# sketch_identifier.net
KiCad netlist of a schematic drawn in Altium Designer
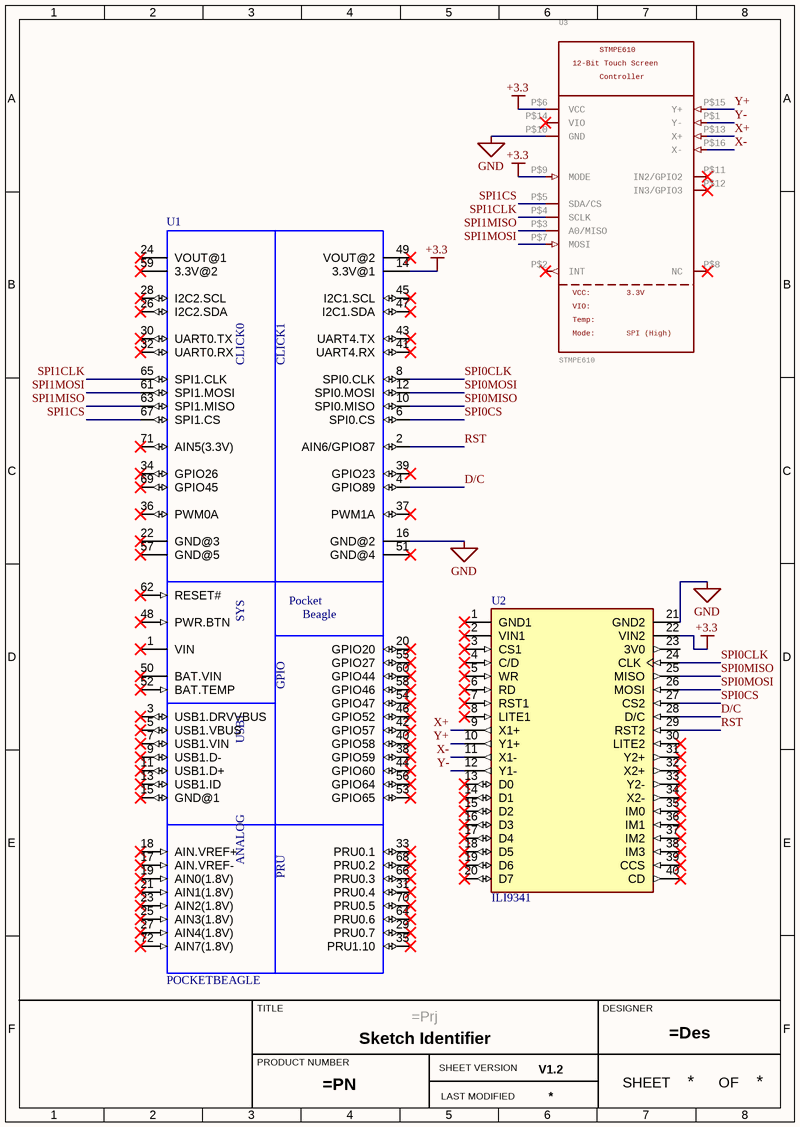
[diagram p0: sketch identifier.SchDoc]

(export (version "E")
  (design (tool "Eeschema 10.0.6"))
  (components
    (comp (ref "U1")
      (value "POCKETBEAGLE")
      (footprint "POCKETBEAGLE")
      (description "OSD3358 PocketBeagle - ARMÂ® CortexÂ®-A8 MPU Embedded Evaluation Board")
      (fields (field (name "MF") "Beagleboard"))
      (libsource (lib "Winson Lin") (part "POCKETBEAGLE"))
    )
    (comp (ref "U2")
      (value "ILI9341")
      (footprint "ADAFRUIT_2478")
      (fields (field (name "MP") "2478") (field (name "MF") "Adafruit Industries"))
      (libsource (lib "Winson Lin") (part "2478"))
    )
    (comp (ref "U3")
      (value "STMPE610")
      (footprint "QFN16_3MM")
      (description "STMPE610 - 12-Bit Touch Screen Controller")
      (fields
        (field (name "VCC") "VCC:")
        (field (name "1.8-3.6V") "3.3V")
        (field (name "VIO") "VIO:")
        (field (name "TEMP") "Temp:")
        (field (name "STMPE610") "STMPE610")
        (field (name "12-BITTOUCHSCREEN") "12-Bit Touch Screen")
        (field (name "CONTROLLER") "Controller")
        (field (name "MODE") "Mode:")
      )
      (libsource (lib "Winson Lin") (part "STMPE610"))
    )
  )
  (nets
    (net (code "1") (name "+3.3") (class "Default")
      (node (ref "U1") (pin "14") (pinfunction "3.3V@1_14") (pintype "power_in"))
      (node (ref "U2") (pin "22") (pinfunction "VIN2_22") (pintype "power_in"))
      (node (ref "U3") (pin "P$6") (pinfunction "VCC_P$6") (pintype "power_in"))
      (node (ref "U3") (pin "P$9") (pinfunction "MODE_P$9") (pintype "input"))
    )
    (net (code "2") (name "/D{slash}C") (class "Default")
      (node (ref "U1") (pin "4") (pinfunction "GPIO89_4") (pintype "bidirectional"))
      (node (ref "U2") (pin "28") (pinfunction "D/C_28") (pintype "input"))
    )
    (net (code "3") (name "/RST") (class "Default")
      (node (ref "U1") (pin "2") (pinfunction "AIN6/GPIO87_2") (pintype "bidirectional"))
      (node (ref "U2") (pin "29") (pinfunction "RST2_29") (pintype "input"))
    )
    (net (code "4") (name "/SPI0CLK") (class "Default")
      (node (ref "U1") (pin "8") (pinfunction "SPI0.CLK_8") (pintype "bidirectional"))
      (node (ref "U2") (pin "24") (pinfunction "CLK_24") (pintype "input"))
    )
    (net (code "5") (name "/SPI0CS") (class "Default")
      (node (ref "U1") (pin "6") (pinfunction "SPI0.CS_6") (pintype "bidirectional"))
      (node (ref "U2") (pin "27") (pinfunction "CS2_27") (pintype "input"))
    )
    (net (code "6") (name "/SPI0MISO") (class "Default")
      (node (ref "U1") (pin "10") (pinfunction "SPI0.MISO_10") (pintype "bidirectional"))
      (node (ref "U2") (pin "25") (pinfunction "MISO_25") (pintype "output"))
    )
    (net (code "7") (name "/SPI0MOSI") (class "Default")
      (node (ref "U1") (pin "12") (pinfunction "SPI0.MOSI_12") (pintype "bidirectional"))
      (node (ref "U2") (pin "26") (pinfunction "MOSI_26") (pintype "input"))
    )
    (net (code "8") (name "/SPI1CLK") (class "Default")
      (node (ref "U1") (pin "65") (pinfunction "SPI1.CLK_65") (pintype "bidirectional"))
      (node (ref "U3") (pin "P$4") (pinfunction "SCLK_P$4") (pintype "bidirectional"))
    )
    (net (code "9") (name "/SPI1CS") (class "Default")
      (node (ref "U1") (pin "67") (pinfunction "SPI1.CS_67") (pintype "bidirectional"))
      (node (ref "U3") (pin "P$5") (pinfunction "SDA/CS_P$5") (pintype "bidirectional"))
    )
    (net (code "10") (name "/SPI1MISO") (class "Default")
      (node (ref "U1") (pin "63") (pinfunction "SPI1.MISO_63") (pintype "bidirectional"))
      (node (ref "U3") (pin "P$3") (pinfunction "A0/MISO_P$3") (pintype "bidirectional"))
    )
    (net (code "11") (name "/SPI1MOSI") (class "Default")
      (node (ref "U1") (pin "61") (pinfunction "SPI1.MOSI_61") (pintype "bidirectional"))
      (node (ref "U3") (pin "P$7") (pinfunction "MOSI_P$7") (pintype "input"))
    )
    (net (code "12") (name "/X+") (class "Default")
      (node (ref "U2") (pin "9") (pinfunction "X1+_9") (pintype "output"))
      (node (ref "U3") (pin "P$13") (pinfunction "X+_P$13") (pintype "input"))
    )
    (net (code "13") (name "/X-") (class "Default")
      (node (ref "U2") (pin "11") (pinfunction "X1-_11") (pintype "output"))
      (node (ref "U3") (pin "P$16") (pinfunction "X-_P$16") (pintype "input"))
    )
    (net (code "14") (name "/Y+") (class "Default")
      (node (ref "U2") (pin "10") (pinfunction "Y1+_10") (pintype "output"))
      (node (ref "U3") (pin "P$15") (pinfunction "Y+_P$15") (pintype "input"))
    )
    (net (code "15") (name "/Y-") (class "Default")
      (node (ref "U2") (pin "12") (pinfunction "Y1-_12") (pintype "output"))
      (node (ref "U3") (pin "P$1") (pinfunction "Y-_P$1") (pintype "input"))
    )
    (net (code "16") (name "GND") (class "Default")
      (node (ref "U1") (pin "16") (pinfunction "GND@2_16") (pintype "power_in"))
      (node (ref "U2") (pin "21") (pinfunction "GND2_21") (pintype "power_in"))
      (node (ref "U3") (pin "P$10") (pinfunction "GND_P$10") (pintype "power_in"))
    )
    (net (code "17") (name "unconnected-(U1-3.3V@2-Pad59)") (class "Default")
      (node (ref "U1") (pin "59") (pinfunction "3.3V@2_59") (pintype "power_in+no_connect"))
    )
    (net (code "18") (name "unconnected-(U1-AIN.VREF+-Pad18)") (class "Default")
      (node (ref "U1") (pin "18") (pinfunction "AIN.VREF+_18") (pintype "input+no_connect"))
    )
    (net (code "19") (name "unconnected-(U1-AIN.VREF--Pad17)") (class "Default")
      (node (ref "U1") (pin "17") (pinfunction "AIN.VREF-_17") (pintype "input+no_connect"))
    )
    (net (code "20") (name "unconnected-(U1-AIN0(1.8V)-Pad19)") (class "Default")
      (node (ref "U1") (pin "19") (pinfunction "AIN0(1.8V)_19") (pintype "input+no_connect"))
    )
    (net (code "21") (name "unconnected-(U1-AIN1(1.8V)-Pad21)") (class "Default")
      (node (ref "U1") (pin "21") (pinfunction "AIN1(1.8V)_21") (pintype "input+no_connect"))
    )
    (net (code "22") (name "unconnected-(U1-AIN2(1.8V)-Pad23)") (class "Default")
      (node (ref "U1") (pin "23") (pinfunction "AIN2(1.8V)_23") (pintype "input+no_connect"))
    )
    (net (code "23") (name "unconnected-(U1-AIN3(1.8V)-Pad25)") (class "Default")
      (node (ref "U1") (pin "25") (pinfunction "AIN3(1.8V)_25") (pintype "input+no_connect"))
    )
    (net (code "24") (name "unconnected-(U1-AIN4(1.8V)-Pad27)") (class "Default")
      (node (ref "U1") (pin "27") (pinfunction "AIN4(1.8V)_27") (pintype "input+no_connect"))
    )
    (net (code "25") (name "unconnected-(U1-AIN5(3.3V)-Pad71)") (class "Default")
      (node (ref "U1") (pin "71") (pinfunction "AIN5(3.3V)_71") (pintype "bidirectional+no_connect"))
    )
    (net (code "26") (name "unconnected-(U1-AIN7(1.8V)-Pad72)") (class "Default")
      (node (ref "U1") (pin "72") (pinfunction "AIN7(1.8V)_72") (pintype "input+no_connect"))
    )
    (net (code "27") (name "unconnected-(U1-BAT.TEMP-Pad52)") (class "Default")
      (node (ref "U1") (pin "52") (pinfunction "BAT.TEMP_52") (pintype "input+no_connect"))
    )
    (net (code "28") (name "unconnected-(U1-BAT.VIN-Pad50)") (class "Default")
      (node (ref "U1") (pin "50") (pinfunction "BAT.VIN_50") (pintype "power_in+no_connect"))
    )
    (net (code "29") (name "unconnected-(U1-GND@1-Pad15)") (class "Default")
      (node (ref "U1") (pin "15") (pinfunction "GND@1_15") (pintype "bidirectional+no_connect"))
    )
    (net (code "30") (name "unconnected-(U1-GND@3-Pad22)") (class "Default")
      (node (ref "U1") (pin "22") (pinfunction "GND@3_22") (pintype "power_in+no_connect"))
    )
    (net (code "31") (name "unconnected-(U1-GND@4-Pad51)") (class "Default")
      (node (ref "U1") (pin "51") (pinfunction "GND@4_51") (pintype "power_in+no_connect"))
    )
    (net (code "32") (name "unconnected-(U1-GND@5-Pad57)") (class "Default")
      (node (ref "U1") (pin "57") (pinfunction "GND@5_57") (pintype "power_in+no_connect"))
    )
    (net (code "33") (name "unconnected-(U1-GPIO20-Pad20)") (class "Default")
      (node (ref "U1") (pin "20") (pinfunction "GPIO20_20") (pintype "bidirectional+no_connect"))
    )
    (net (code "34") (name "unconnected-(U1-GPIO23-Pad39)") (class "Default")
      (node (ref "U1") (pin "39") (pinfunction "GPIO23_39") (pintype "bidirectional+no_connect"))
    )
    (net (code "35") (name "unconnected-(U1-GPIO26-Pad34)") (class "Default")
      (node (ref "U1") (pin "34") (pinfunction "GPIO26_34") (pintype "bidirectional+no_connect"))
    )
    (net (code "36") (name "unconnected-(U1-GPIO27-Pad55)") (class "Default")
      (node (ref "U1") (pin "55") (pinfunction "GPIO27_55") (pintype "bidirectional+no_connect"))
    )
    (net (code "37") (name "unconnected-(U1-GPIO44-Pad60)") (class "Default")
      (node (ref "U1") (pin "60") (pinfunction "GPIO44_60") (pintype "bidirectional+no_connect"))
    )
    (net (code "38") (name "unconnected-(U1-GPIO45-Pad69)") (class "Default")
      (node (ref "U1") (pin "69") (pinfunction "GPIO45_69") (pintype "bidirectional+no_connect"))
    )
    (net (code "39") (name "unconnected-(U1-GPIO46-Pad58)") (class "Default")
      (node (ref "U1") (pin "58") (pinfunction "GPIO46_58") (pintype "bidirectional+no_connect"))
    )
    (net (code "40") (name "unconnected-(U1-GPIO47-Pad54)") (class "Default")
      (node (ref "U1") (pin "54") (pinfunction "GPIO47_54") (pintype "bidirectional+no_connect"))
    )
    (net (code "41") (name "unconnected-(U1-GPIO52-Pad46)") (class "Default")
      (node (ref "U1") (pin "46") (pinfunction "GPIO52_46") (pintype "bidirectional+no_connect"))
    )
    (net (code "42") (name "unconnected-(U1-GPIO57-Pad42)") (class "Default")
      (node (ref "U1") (pin "42") (pinfunction "GPIO57_42") (pintype "bidirectional+no_connect"))
    )
    (net (code "43") (name "unconnected-(U1-GPIO58-Pad40)") (class "Default")
      (node (ref "U1") (pin "40") (pinfunction "GPIO58_40") (pintype "bidirectional+no_connect"))
    )
    (net (code "44") (name "unconnected-(U1-GPIO59-Pad38)") (class "Default")
      (node (ref "U1") (pin "38") (pinfunction "GPIO59_38") (pintype "bidirectional+no_connect"))
    )
    (net (code "45") (name "unconnected-(U1-GPIO60-Pad44)") (class "Default")
      (node (ref "U1") (pin "44") (pinfunction "GPIO60_44") (pintype "bidirectional+no_connect"))
    )
    (net (code "46") (name "unconnected-(U1-GPIO64-Pad56)") (class "Default")
      (node (ref "U1") (pin "56") (pinfunction "GPIO64_56") (pintype "bidirectional+no_connect"))
    )
    (net (code "47") (name "unconnected-(U1-GPIO65-Pad53)") (class "Default")
      (node (ref "U1") (pin "53") (pinfunction "GPIO65_53") (pintype "bidirectional+no_connect"))
    )
    (net (code "48") (name "unconnected-(U1-I2C1.SCL-Pad45)") (class "Default")
      (node (ref "U1") (pin "45") (pinfunction "I2C1.SCL_45") (pintype "bidirectional+no_connect"))
    )
    (net (code "49") (name "unconnected-(U1-I2C1.SDA-Pad47)") (class "Default")
      (node (ref "U1") (pin "47") (pinfunction "I2C1.SDA_47") (pintype "bidirectional+no_connect"))
    )
    (net (code "50") (name "unconnected-(U1-I2C2.SCL-Pad28)") (class "Default")
      (node (ref "U1") (pin "28") (pinfunction "I2C2.SCL_28") (pintype "bidirectional+no_connect"))
    )
    (net (code "51") (name "unconnected-(U1-I2C2.SDA-Pad26)") (class "Default")
      (node (ref "U1") (pin "26") (pinfunction "I2C2.SDA_26") (pintype "bidirectional+no_connect"))
    )
    (net (code "52") (name "unconnected-(U1-PRU0.1-Pad33)") (class "Default")
      (node (ref "U1") (pin "33") (pinfunction "PRU0.1_33") (pintype "bidirectional+no_connect"))
    )
    (net (code "53") (name "unconnected-(U1-PRU0.2-Pad68)") (class "Default")
      (node (ref "U1") (pin "68") (pinfunction "PRU0.2_68") (pintype "bidirectional+no_connect"))
    )
    (net (code "54") (name "unconnected-(U1-PRU0.3-Pad66)") (class "Default")
      (node (ref "U1") (pin "66") (pinfunction "PRU0.3_66") (pintype "bidirectional+no_connect"))
    )
    (net (code "55") (name "unconnected-(U1-PRU0.4-Pad31)") (class "Default")
      (node (ref "U1") (pin "31") (pinfunction "PRU0.4_31") (pintype "bidirectional+no_connect"))
    )
    (net (code "56") (name "unconnected-(U1-PRU0.5-Pad70)") (class "Default")
      (node (ref "U1") (pin "70") (pinfunction "PRU0.5_70") (pintype "bidirectional+no_connect"))
    )
    (net (code "57") (name "unconnected-(U1-PRU0.6-Pad64)") (class "Default")
      (node (ref "U1") (pin "64") (pinfunction "PRU0.6_64") (pintype "bidirectional+no_connect"))
    )
    (net (code "58") (name "unconnected-(U1-PRU0.7-Pad29)") (class "Default")
      (node (ref "U1") (pin "29") (pinfunction "PRU0.7_29") (pintype "bidirectional+no_connect"))
    )
    (net (code "59") (name "unconnected-(U1-PRU1.10-Pad35)") (class "Default")
      (node (ref "U1") (pin "35") (pinfunction "PRU1.10_35") (pintype "bidirectional+no_connect"))
    )
    (net (code "60") (name "unconnected-(U1-PWM0A-Pad36)") (class "Default")
      (node (ref "U1") (pin "36") (pinfunction "PWM0A_36") (pintype "bidirectional+no_connect"))
    )
    (net (code "61") (name "unconnected-(U1-PWM1A-Pad37)") (class "Default")
      (node (ref "U1") (pin "37") (pinfunction "PWM1A_37") (pintype "bidirectional+no_connect"))
    )
    (net (code "62") (name "unconnected-(U1-PWR.BTN-Pad48)") (class "Default")
      (node (ref "U1") (pin "48") (pinfunction "PWR.BTN_48") (pintype "input+no_connect"))
    )
    (net (code "63") (name "unconnected-(U1-RESET#-Pad62)") (class "Default")
      (node (ref "U1") (pin "62") (pinfunction "RESET#_62") (pintype "input+no_connect"))
    )
    (net (code "64") (name "unconnected-(U1-UART0.RX-Pad32)") (class "Default")
      (node (ref "U1") (pin "32") (pinfunction "UART0.RX_32") (pintype "bidirectional+no_connect"))
    )
    (net (code "65") (name "unconnected-(U1-UART0.TX-Pad30)") (class "Default")
      (node (ref "U1") (pin "30") (pinfunction "UART0.TX_30") (pintype "bidirectional+no_connect"))
    )
    (net (code "66") (name "unconnected-(U1-UART4.RX-Pad41)") (class "Default")
      (node (ref "U1") (pin "41") (pinfunction "UART4.RX_41") (pintype "bidirectional+no_connect"))
    )
    (net (code "67") (name "unconnected-(U1-UART4.TX-Pad43)") (class "Default")
      (node (ref "U1") (pin "43") (pinfunction "UART4.TX_43") (pintype "bidirectional+no_connect"))
    )
    (net (code "68") (name "unconnected-(U1-USB1.D+-Pad11)") (class "Default")
      (node (ref "U1") (pin "11") (pinfunction "USB1.D+_11") (pintype "bidirectional+no_connect"))
    )
    (net (code "69") (name "unconnected-(U1-USB1.D--Pad9)") (class "Default")
      (node (ref "U1") (pin "9") (pinfunction "USB1.D-_9") (pintype "bidirectional+no_connect"))
    )
    (net (code "70") (name "unconnected-(U1-USB1.DRVVBUS-Pad3)") (class "Default")
      (node (ref "U1") (pin "3") (pinfunction "USB1.DRVVBUS_3") (pintype "bidirectional+no_connect"))
    )
    (net (code "71") (name "unconnected-(U1-USB1.ID-Pad13)") (class "Default")
      (node (ref "U1") (pin "13") (pinfunction "USB1.ID_13") (pintype "bidirectional+no_connect"))
    )
    (net (code "72") (name "unconnected-(U1-USB1.VBUS-Pad5)") (class "Default")
      (node (ref "U1") (pin "5") (pinfunction "USB1.VBUS_5") (pintype "bidirectional+no_connect"))
    )
    (net (code "73") (name "unconnected-(U1-USB1.VIN-Pad7)") (class "Default")
      (node (ref "U1") (pin "7") (pinfunction "USB1.VIN_7") (pintype "bidirectional+no_connect"))
    )
    (net (code "74") (name "unconnected-(U1-VIN-Pad1)") (class "Default")
      (node (ref "U1") (pin "1") (pinfunction "VIN_1") (pintype "power_in+no_connect"))
    )
    (net (code "75") (name "unconnected-(U1-VOUT@1-Pad24)") (class "Default")
      (node (ref "U1") (pin "24") (pinfunction "VOUT@1_24") (pintype "power_in+no_connect"))
    )
    (net (code "76") (name "unconnected-(U1-VOUT@2-Pad49)") (class "Default")
      (node (ref "U1") (pin "49") (pinfunction "VOUT@2_49") (pintype "power_in+no_connect"))
    )
    (net (code "77") (name "unconnected-(U2-3V0-Pad23)") (class "Default")
      (node (ref "U2") (pin "23") (pinfunction "3V0_23") (pintype "output"))
    )
    (net (code "78") (name "unconnected-(U2-CCS-Pad39)") (class "Default")
      (node (ref "U2") (pin "39") (pinfunction "CCS_39") (pintype "input+no_connect"))
    )
    (net (code "79") (name "unconnected-(U2-CD-Pad40)") (class "Default")
      (node (ref "U2") (pin "40") (pinfunction "CD_40") (pintype "output+no_connect"))
    )
    (net (code "80") (name "unconnected-(U2-CS1-Pad3)") (class "Default")
      (node (ref "U2") (pin "3") (pinfunction "CS1_3") (pintype "input+no_connect"))
    )
    (net (code "81") (name "unconnected-(U2-C{slash}D-Pad4)") (class "Default")
      (node (ref "U2") (pin "4") (pinfunction "C/D_4") (pintype "input+no_connect"))
    )
    (net (code "82") (name "unconnected-(U2-D0-Pad13)") (class "Default")
      (node (ref "U2") (pin "13") (pinfunction "D0_13") (pintype "bidirectional+no_connect"))
    )
    (net (code "83") (name "unconnected-(U2-D1-Pad14)") (class "Default")
      (node (ref "U2") (pin "14") (pinfunction "D1_14") (pintype "bidirectional+no_connect"))
    )
    (net (code "84") (name "unconnected-(U2-D2-Pad15)") (class "Default")
      (node (ref "U2") (pin "15") (pinfunction "D2_15") (pintype "bidirectional+no_connect"))
    )
    (net (code "85") (name "unconnected-(U2-D3-Pad16)") (class "Default")
      (node (ref "U2") (pin "16") (pinfunction "D3_16") (pintype "bidirectional+no_connect"))
    )
    (net (code "86") (name "unconnected-(U2-D4-Pad17)") (class "Default")
      (node (ref "U2") (pin "17") (pinfunction "D4_17") (pintype "bidirectional+no_connect"))
    )
    (net (code "87") (name "unconnected-(U2-D5-Pad18)") (class "Default")
      (node (ref "U2") (pin "18") (pinfunction "D5_18") (pintype "bidirectional+no_connect"))
    )
    (net (code "88") (name "unconnected-(U2-D6-Pad19)") (class "Default")
      (node (ref "U2") (pin "19") (pinfunction "D6_19") (pintype "bidirectional+no_connect"))
    )
    (net (code "89") (name "unconnected-(U2-D7-Pad20)") (class "Default")
      (node (ref "U2") (pin "20") (pinfunction "D7_20") (pintype "bidirectional+no_connect"))
    )
    (net (code "90") (name "unconnected-(U2-GND1-Pad1)") (class "Default")
      (node (ref "U2") (pin "1") (pinfunction "GND1_1") (pintype "power_in+no_connect"))
    )
    (net (code "91") (name "unconnected-(U2-IM0-Pad35)") (class "Default")
      (node (ref "U2") (pin "35") (pinfunction "IM0_35") (pintype "input+no_connect"))
    )
    (net (code "92") (name "unconnected-(U2-IM1-Pad36)") (class "Default")
      (node (ref "U2") (pin "36") (pinfunction "IM1_36") (pintype "input+no_connect"))
    )
    (net (code "93") (name "unconnected-(U2-IM2-Pad37)") (class "Default")
      (node (ref "U2") (pin "37") (pinfunction "IM2_37") (pintype "input+no_connect"))
    )
    (net (code "94") (name "unconnected-(U2-IM3-Pad38)") (class "Default")
      (node (ref "U2") (pin "38") (pinfunction "IM3_38") (pintype "input+no_connect"))
    )
    (net (code "95") (name "unconnected-(U2-LITE1-Pad8)") (class "Default")
      (node (ref "U2") (pin "8") (pinfunction "LITE1_8") (pintype "input+no_connect"))
    )
    (net (code "96") (name "unconnected-(U2-LITE2-Pad30)") (class "Default")
      (node (ref "U2") (pin "30") (pinfunction "LITE2_30") (pintype "input+no_connect"))
    )
    (net (code "97") (name "unconnected-(U2-RD-Pad6)") (class "Default")
      (node (ref "U2") (pin "6") (pinfunction "RD_6") (pintype "input+no_connect"))
    )
    (net (code "98") (name "unconnected-(U2-RST1-Pad7)") (class "Default")
      (node (ref "U2") (pin "7") (pinfunction "RST1_7") (pintype "input+no_connect"))
    )
    (net (code "99") (name "unconnected-(U2-VIN1-Pad2)") (class "Default")
      (node (ref "U2") (pin "2") (pinfunction "VIN1_2") (pintype "power_in+no_connect"))
    )
    (net (code "100") (name "unconnected-(U2-WR-Pad5)") (class "Default")
      (node (ref "U2") (pin "5") (pinfunction "WR_5") (pintype "input+no_connect"))
    )
    (net (code "101") (name "unconnected-(U2-X2+-Pad32)") (class "Default")
      (node (ref "U2") (pin "32") (pinfunction "X2+_32") (pintype "output+no_connect"))
    )
    (net (code "102") (name "unconnected-(U2-X2--Pad34)") (class "Default")
      (node (ref "U2") (pin "34") (pinfunction "X2-_34") (pintype "output+no_connect"))
    )
    (net (code "103") (name "unconnected-(U2-Y2+-Pad31)") (class "Default")
      (node (ref "U2") (pin "31") (pinfunction "Y2+_31") (pintype "output+no_connect"))
    )
    (net (code "104") (name "unconnected-(U2-Y2--Pad33)") (class "Default")
      (node (ref "U2") (pin "33") (pinfunction "Y2-_33") (pintype "output+no_connect"))
    )
    (net (code "105") (name "unconnected-(U3-IN2{slash}GPIO2-PadP$11)") (class "Default")
      (node (ref "U3") (pin "P$11") (pinfunction "IN2/GPIO2_P$11") (pintype "bidirectional+no_connect"))
    )
    (net (code "106") (name "unconnected-(U3-IN3{slash}GPIO3-PadP$12)") (class "Default")
      (node (ref "U3") (pin "P$12") (pinfunction "IN3/GPIO3_P$12") (pintype "bidirectional+no_connect"))
    )
    (net (code "107") (name "unconnected-(U3-INT-PadP$2)") (class "Default")
      (node (ref "U3") (pin "P$2") (pinfunction "INT_P$2") (pintype "output+no_connect"))
    )
    (net (code "108") (name "unconnected-(U3-NC-PadP$8)") (class "Default")
      (node (ref "U3") (pin "P$8") (pinfunction "NC_P$8") (pintype "passive+no_connect"))
    )
    (net (code "109") (name "unconnected-(U3-VIO-PadP$14)") (class "Default")
      (node (ref "U3") (pin "P$14") (pinfunction "VIO_P$14") (pintype "power_in+no_connect"))
    )
  )
)
